# PCB_Project.net
KiCad netlist of a schematic drawn in EasyEDA Pro
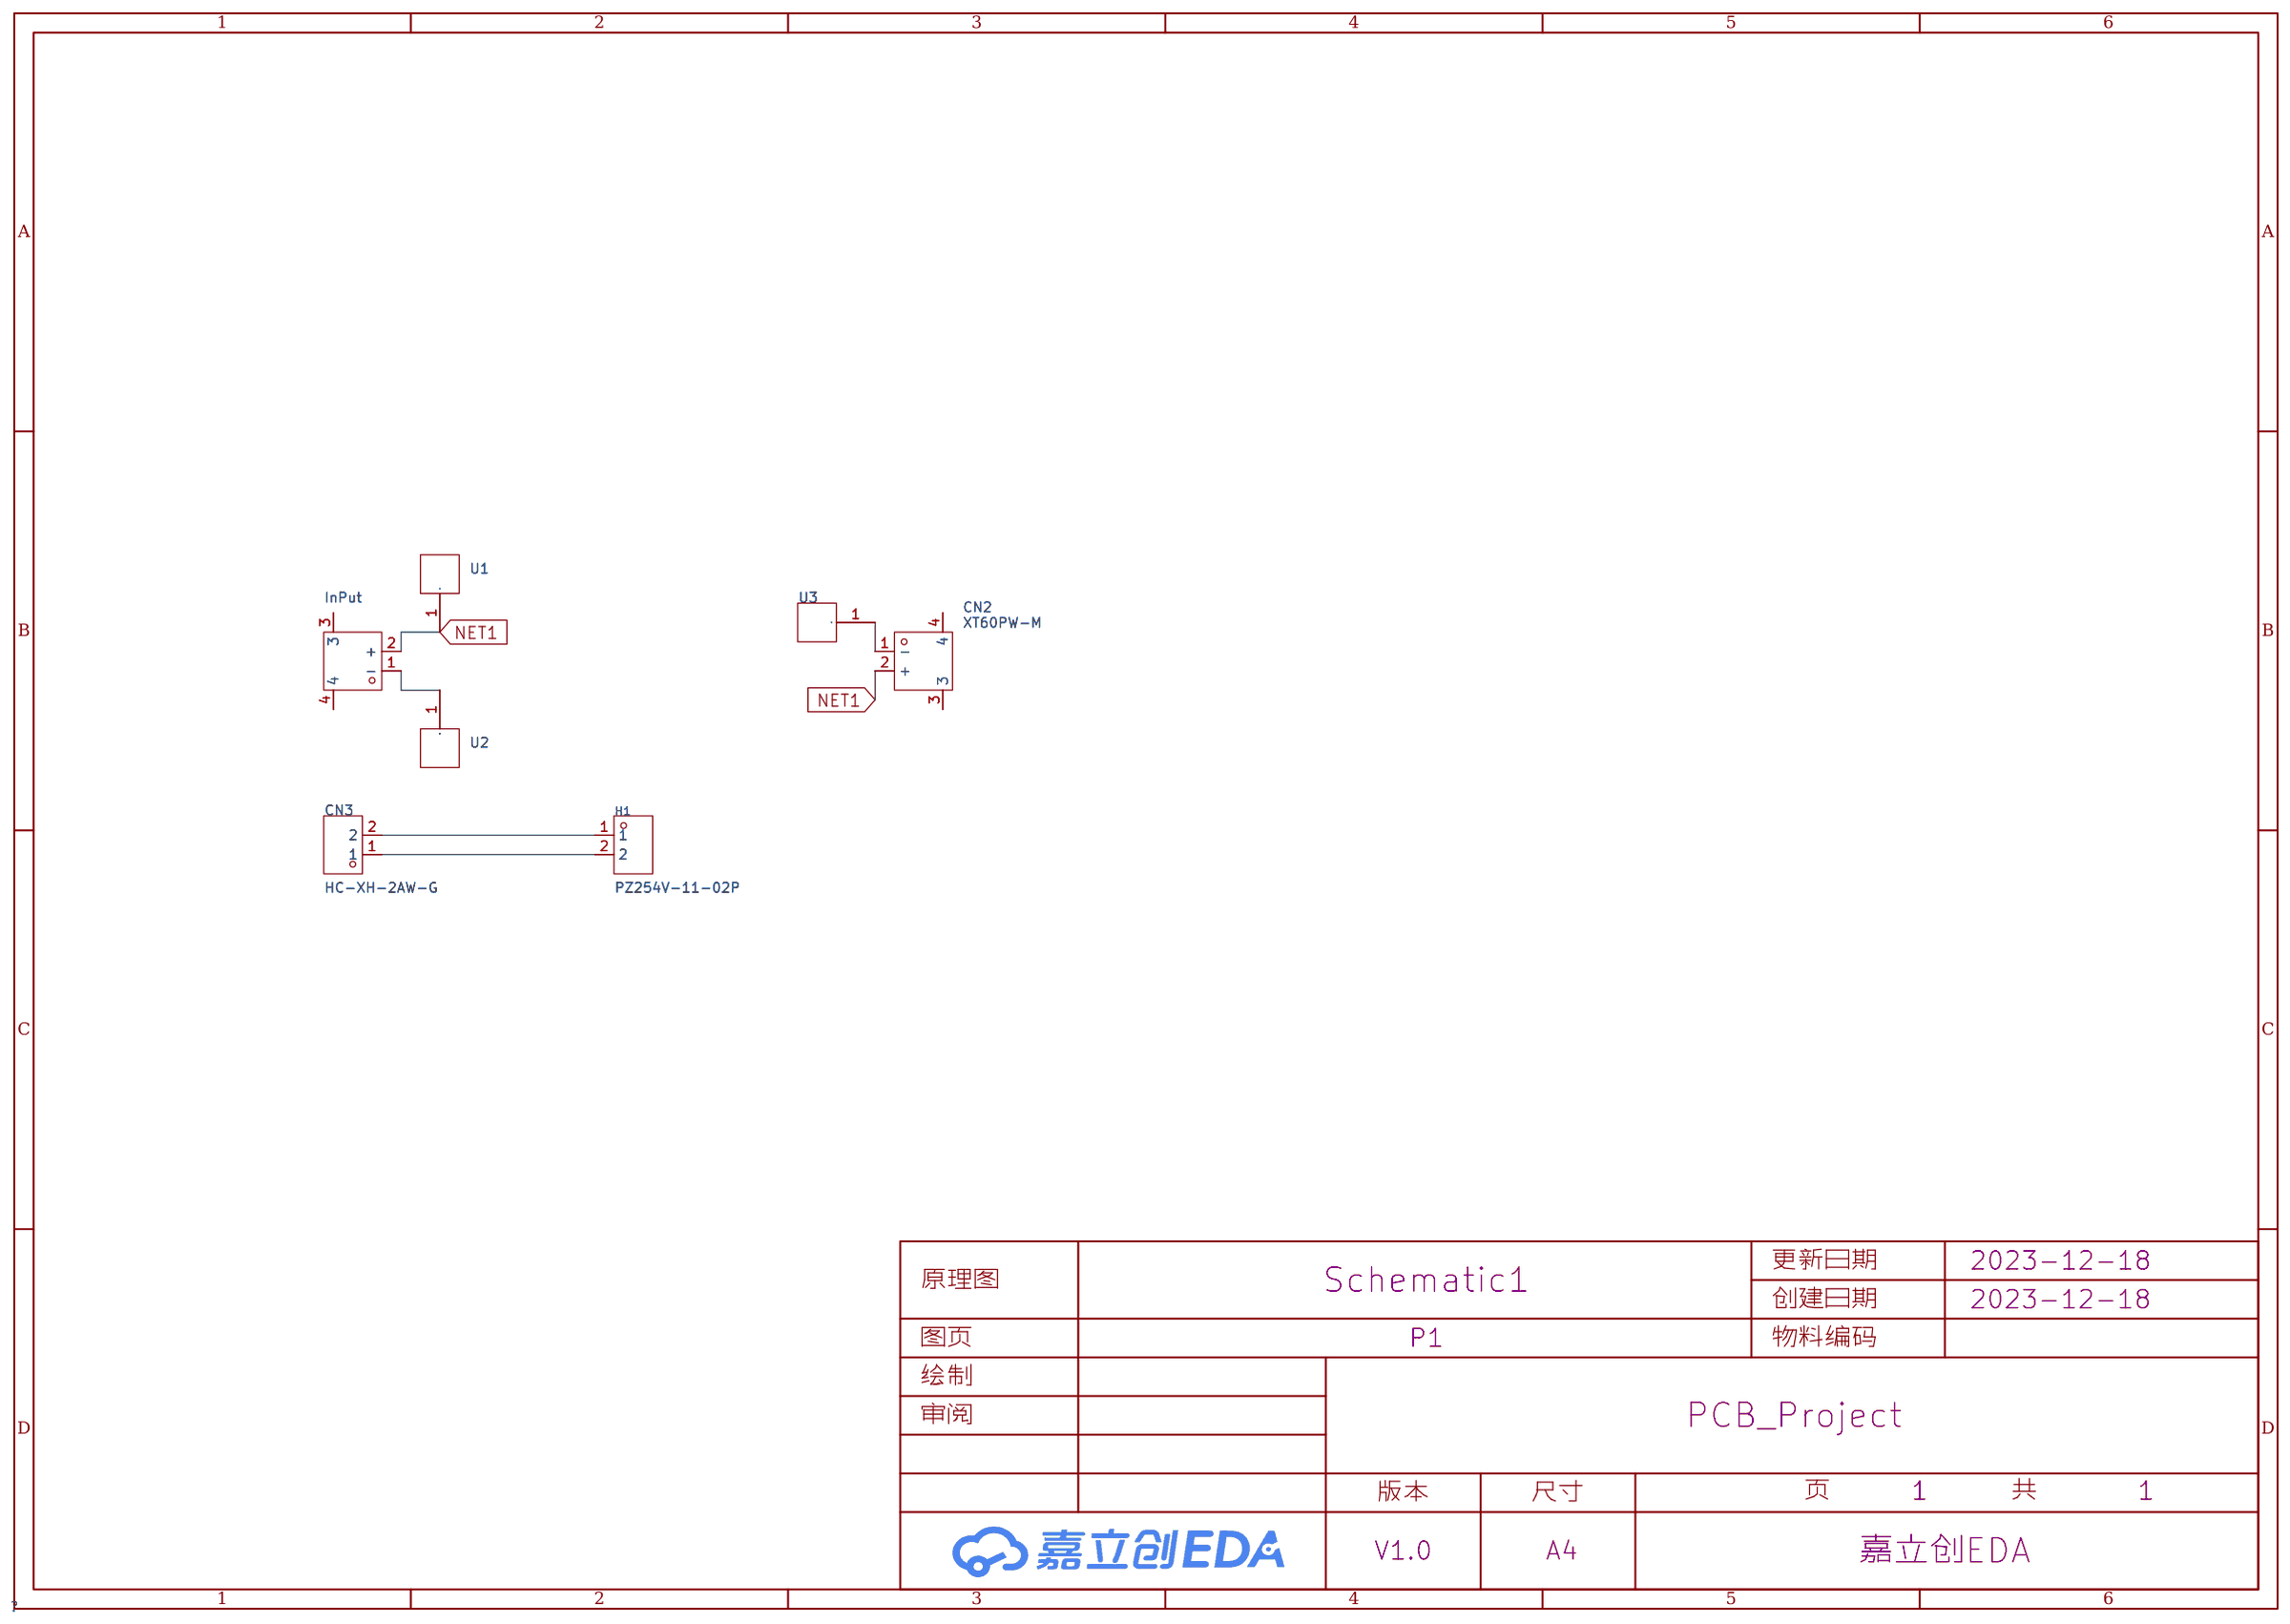
[diagram p0: schematic sheet]

(export (version "E")
  (design (tool "Eeschema 10.0.6"))
  (components
    (comp (ref "CN2")
      (value "XT60PW-M")
      (footprint "easyedapro:CONN-TH_XT60PW-M")
      (description "类别:-;类型1:-;")
      (fields (field (name "Manufacturer") "AMASS(艾迈斯)"))
      (libsource (lib "easyedapro") (part "XT60PW-M"))
    )
    (comp (ref "CN3")
      (value "HC-XH-2AW-G")
      (footprint "easyedapro:CONN-TH_2P-P2.50_HC-XH-2AW-G")
      (description "插针结构:1x2P;间距:2.54mm;安装方式:弯插;行距:2.54mm;总PIN数:2P;排数:1;每排PIN数:2;参考系列:XH;额定电流:3A;工作温度范围:-25°C~+85°C;")
      (fields (field (name "Manufacturer") "HCTL(华灿天禄)"))
      (libsource (lib "easyedapro") (part "HC-XH-2AW-G"))
    )
    (comp (ref "H1")
      (value "PZ254V-11-02P")
      (footprint "easyedapro:HDR-TH_2P-P2.54-V-M")
      (fields (field (name "Manufacturer") "XFCN(兴飞)"))
      (libsource (lib "easyedapro") (part "PZ254V-11-02P"))
    )
    (comp (ref "InPut")
      (value "XT60PW-M")
      (footprint "easyedapro:CONN-TH_XT60PW-M")
      (description "类别:-;类型1:-;")
      (fields (field (name "Manufacturer") "AMASS(艾迈斯)"))
      (libsource (lib "easyedapro") (part "XT60PW-M"))
    )
    (comp (ref "U1")
      (value "~")
      (footprint "easyedapro:过孔焊盘(1Px3mm)")
      (libsource (lib "easyedapro") (part "过孔焊盘(1Px3mm)"))
    )
    (comp (ref "U2")
      (value "~")
      (footprint "easyedapro:过孔焊盘(1Px3mm)")
      (libsource (lib "easyedapro") (part "过孔焊盘(1Px3mm)"))
    )
    (comp (ref "U3")
      (value "~")
      (footprint "easyedapro:过孔焊盘(1Px3mm)")
      (libsource (lib "easyedapro") (part "过孔焊盘(1Px3mm)"))
    )
  )
  (nets
    (net (code "1") (name "NET1") (class "Default")
      (node (ref "CN2") (pin "2") (pinfunction "+_2") (pintype "unspecified"))
      (node (ref "InPut") (pin "2") (pinfunction "+_2") (pintype "unspecified"))
      (node (ref "U1") (pin "1") (pinfunction "1_1") (pintype "input"))
    )
    (net (code "2") (name "Net-(CN2--)") (class "Default")
      (node (ref "CN2") (pin "1") (pinfunction "-_1") (pintype "unspecified"))
      (node (ref "U3") (pin "1") (pinfunction "1_1") (pintype "input"))
    )
    (net (code "3") (name "Net-(CN3-Pad1)") (class "Default")
      (node (ref "CN3") (pin "1") (pinfunction "1_1") (pintype "unspecified"))
      (node (ref "H1") (pin "2") (pinfunction "2_2") (pintype "input"))
    )
    (net (code "4") (name "Net-(CN3-Pad2)") (class "Default")
      (node (ref "CN3") (pin "2") (pinfunction "2_2") (pintype "unspecified"))
      (node (ref "H1") (pin "1") (pinfunction "1_1") (pintype "input"))
    )
    (net (code "5") (name "Net-(InPut--)") (class "Default")
      (node (ref "InPut") (pin "1") (pinfunction "-_1") (pintype "unspecified"))
      (node (ref "U2") (pin "1") (pinfunction "1_1") (pintype "input"))
    )
    (net (code "6") (name "unconnected-(CN2-Pad3)") (class "Default")
      (node (ref "CN2") (pin "3") (pinfunction "3_3") (pintype "unspecified"))
    )
    (net (code "7") (name "unconnected-(CN2-Pad4)") (class "Default")
      (node (ref "CN2") (pin "4") (pinfunction "4_4") (pintype "unspecified"))
    )
    (net (code "8") (name "unconnected-(InPut-Pad3)") (class "Default")
      (node (ref "InPut") (pin "3") (pinfunction "3_3") (pintype "unspecified"))
    )
    (net (code "9") (name "unconnected-(InPut-Pad4)") (class "Default")
      (node (ref "InPut") (pin "4") (pinfunction "4_4") (pintype "unspecified"))
    )
  )
)
